# PressureSensor_PCB.net
KiCad netlist of a schematic drawn in Altium Designer
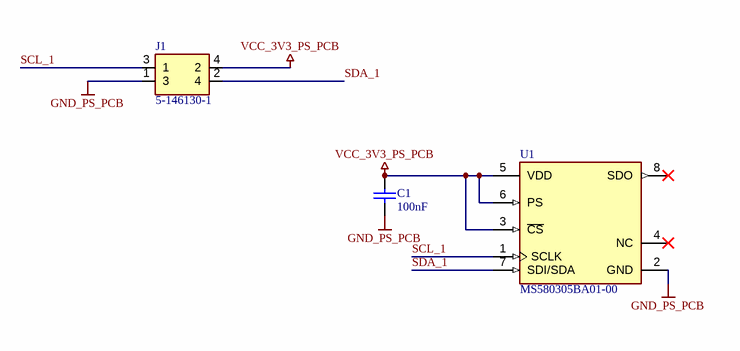
[diagram p0: PressureSensor_PCB.SchDoc]

(export (version "E")
  (design (tool "Eeschema 10.0.6"))
  (components
    (comp (ref "C1")
      (value "100nF")
      (footprint "CAPC2013X140X50NL20T25")
      (fields
        (field (name "PART NUMBER") "08055C104K4Z2A")
        (field (name "MANUFACTURER") "AVX Interconnect / Elco")
      )
      (libsource (lib "Altium Content Vault") (part "CAP"))
    )
    (comp (ref "J1")
      (value "5-146130-1")
      (footprint "5-146130-1:TE_5-146130-1")
      (description "AMPMODU 4 Position Surface Mount Dual Row Straight 2.54 mm Breakaway Header")
      (fields (field (name "MF") "{'manufacturer': u'TE Connectivity'}"))
      (libsource (lib "*") (part "5-146130-1"))
    )
    (comp (ref "U1")
      (value "MS580305BA01-00")
      (footprint "FP-MS580301BA01-00-MFG")
      (description "MINIATURE ALTIMETER MODULE")
      (fields
        (field (name "MANUFACTURER PART NUMBER") "MS580301BA01-00")
        (field (name "MANUFACTURER") "TE Connectivity")
      )
      (libsource (lib "Altium Content Vault") (part "12a5185c47872775e691a69d0eb4388"))
    )
  )
  (nets
    (net (code "1") (name "/SCL_1") (class "Default")
      (node (ref "J1") (pin "3") (pinfunction "1_3") (pintype "passive"))
      (node (ref "U1") (pin "1") (pinfunction "SCLK_1") (pintype "input"))
    )
    (net (code "2") (name "/SDA_1") (class "Default")
      (node (ref "J1") (pin "2") (pinfunction "4_2") (pintype "passive"))
      (node (ref "U1") (pin "7") (pinfunction "SDI/SDA_7") (pintype "input"))
    )
    (net (code "3") (name "GND_PS_PCB") (class "Default")
      (node (ref "C1") (pin "1") (pinfunction "1_1") (pintype "passive"))
      (node (ref "J1") (pin "1") (pinfunction "3_1") (pintype "passive"))
      (node (ref "U1") (pin "2") (pinfunction "GND_2") (pintype "power_in"))
    )
    (net (code "4") (name "VCC_3V3_PS_PCB") (class "Default")
      (node (ref "C1") (pin "2") (pinfunction "2_2") (pintype "passive"))
      (node (ref "J1") (pin "4") (pinfunction "2_4") (pintype "passive"))
      (node (ref "U1") (pin "3") (pinfunction "~{CS}_3") (pintype "input"))
      (node (ref "U1") (pin "5") (pinfunction "VDD_5") (pintype "power_in"))
      (node (ref "U1") (pin "6") (pinfunction "PS_6") (pintype "input"))
    )
    (net (code "5") (name "unconnected-(U1-NC-Pad4)") (class "Default")
      (node (ref "U1") (pin "4") (pinfunction "NC_4") (pintype "passive+no_connect"))
    )
    (net (code "6") (name "unconnected-(U1-SDO-Pad8)") (class "Default")
      (node (ref "U1") (pin "8") (pinfunction "SDO_8") (pintype "output+no_connect"))
    )
  )
)
